# Chipset.net
KiCad netlist of a schematic drawn in Altium Designer
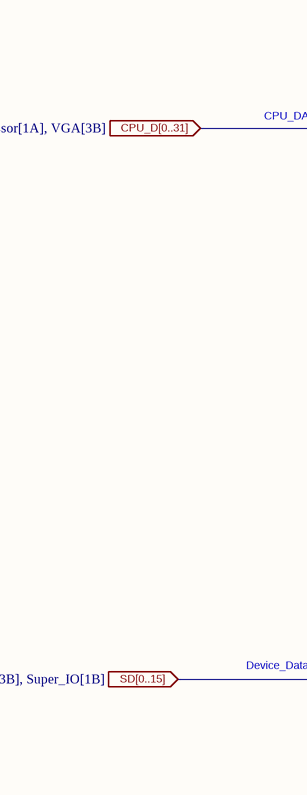
[diagram p0: Chipset.SchDoc, top left]
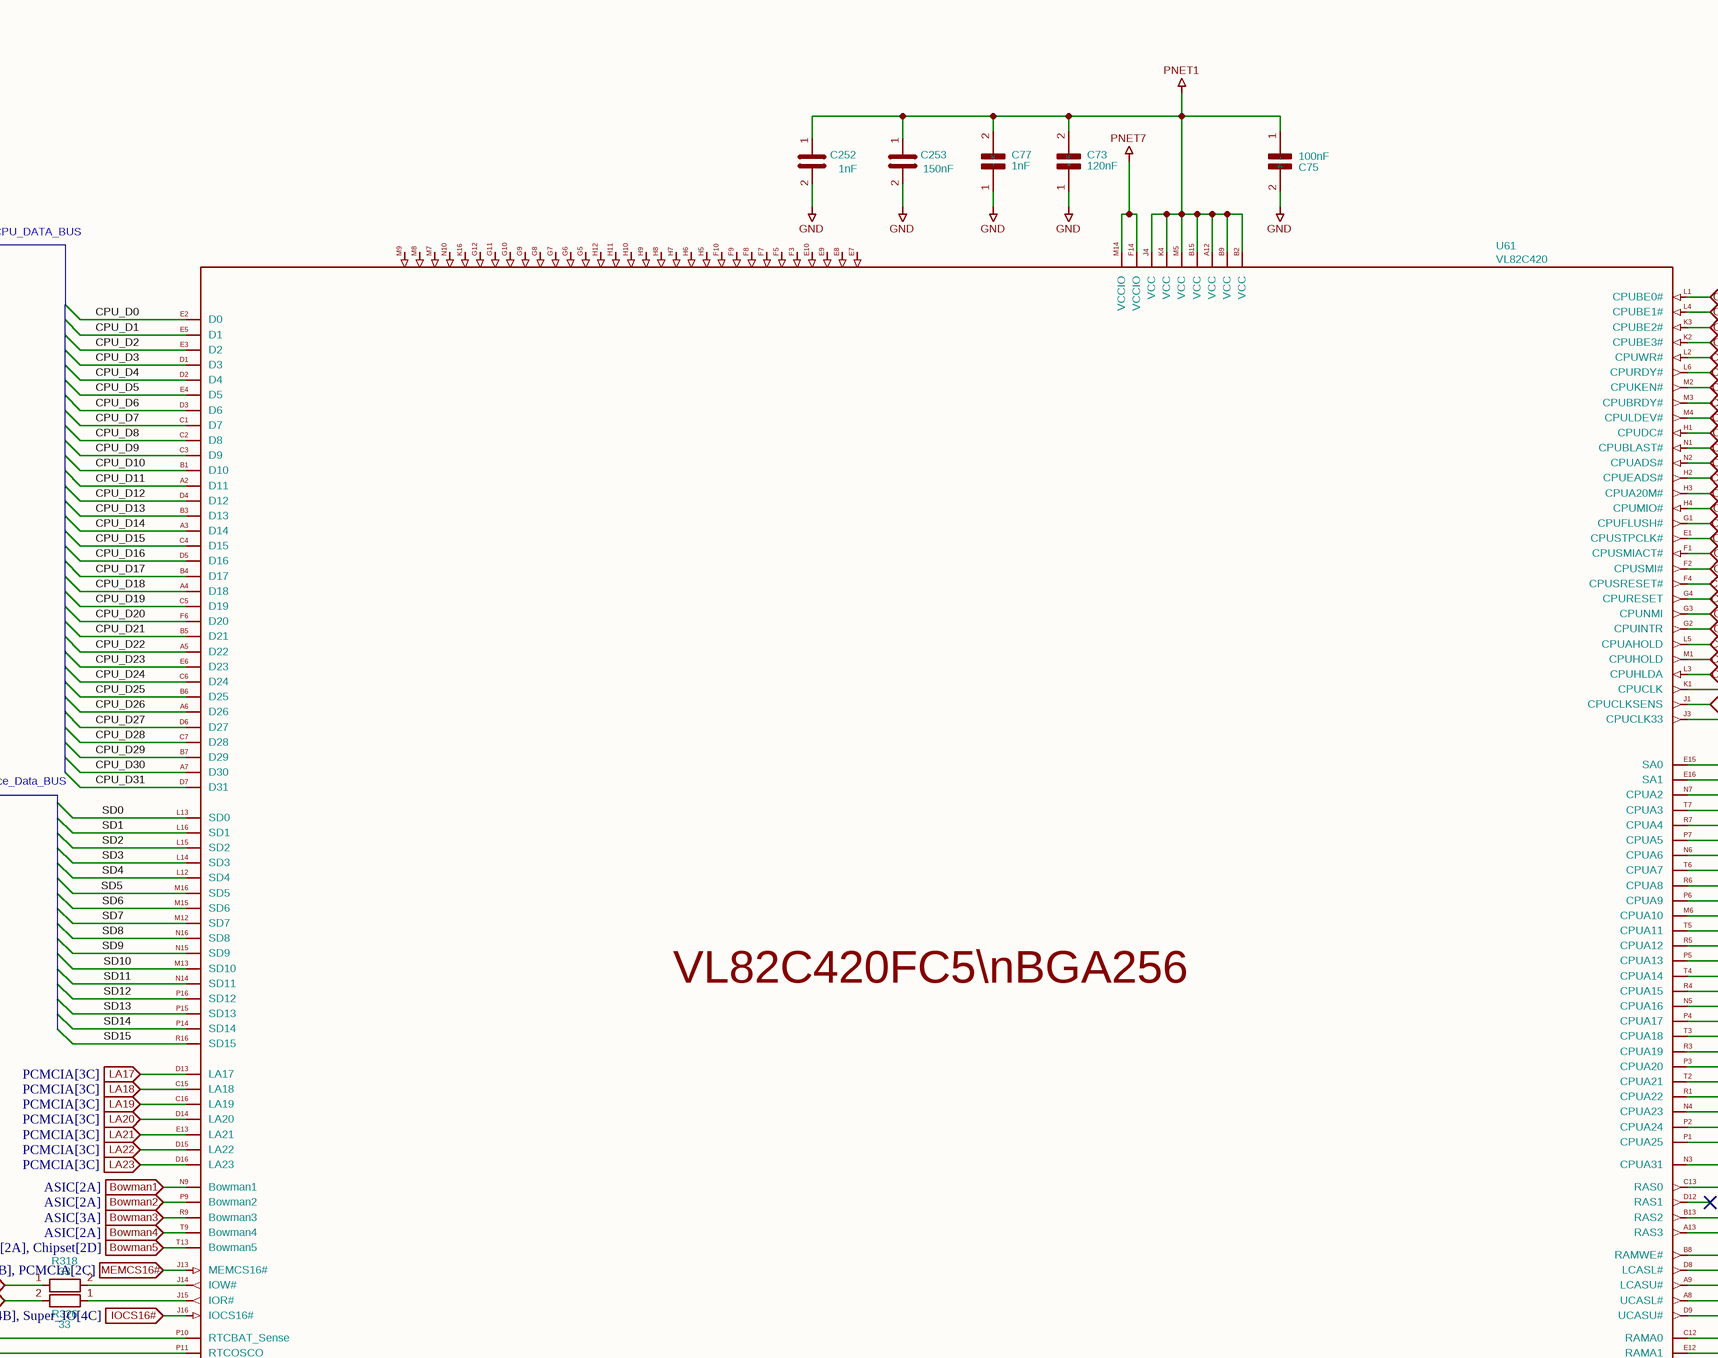
[diagram p1: Chipset.SchDoc, top middle]
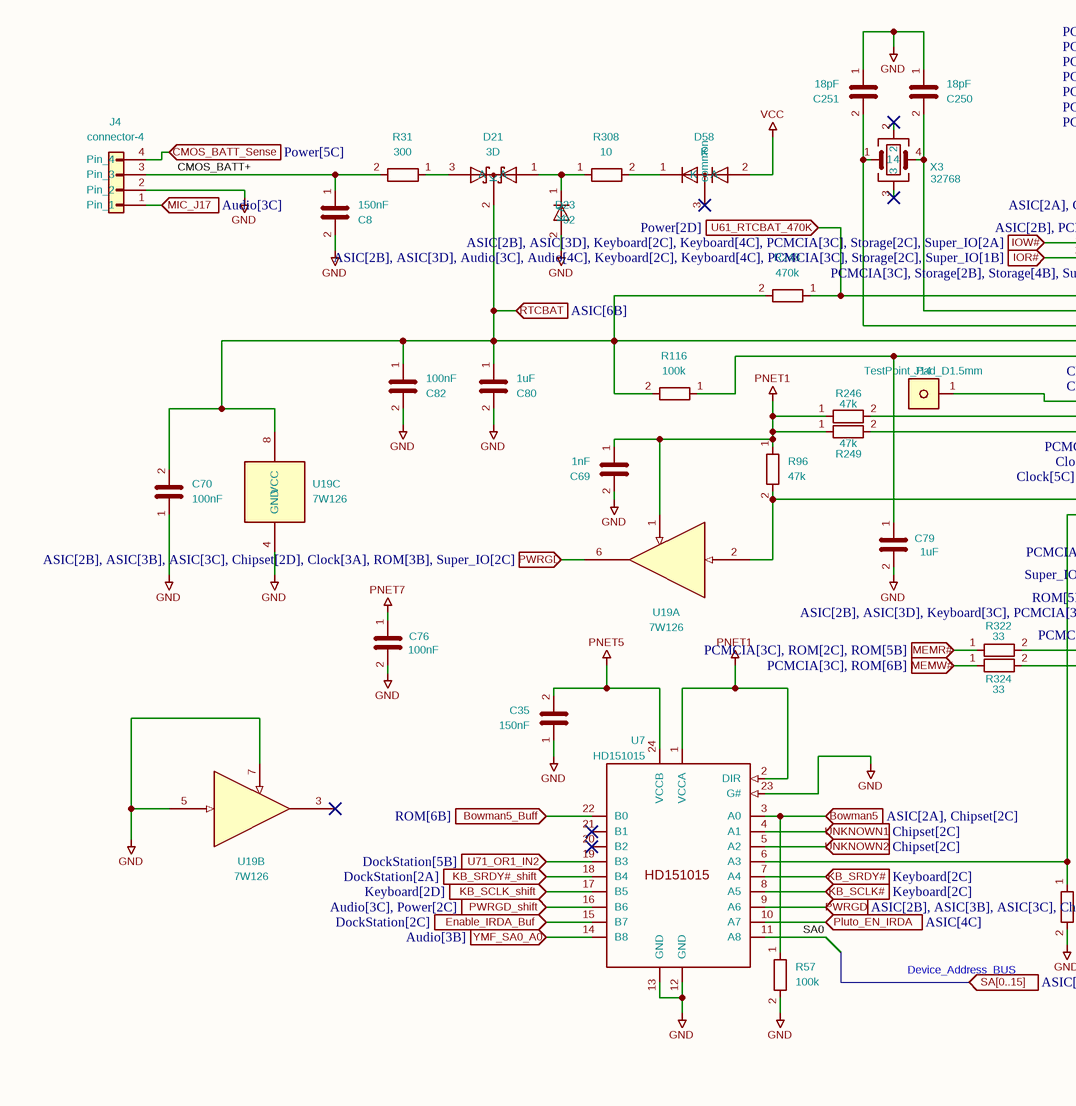
[diagram p2: Chipset.SchDoc, bottom left]
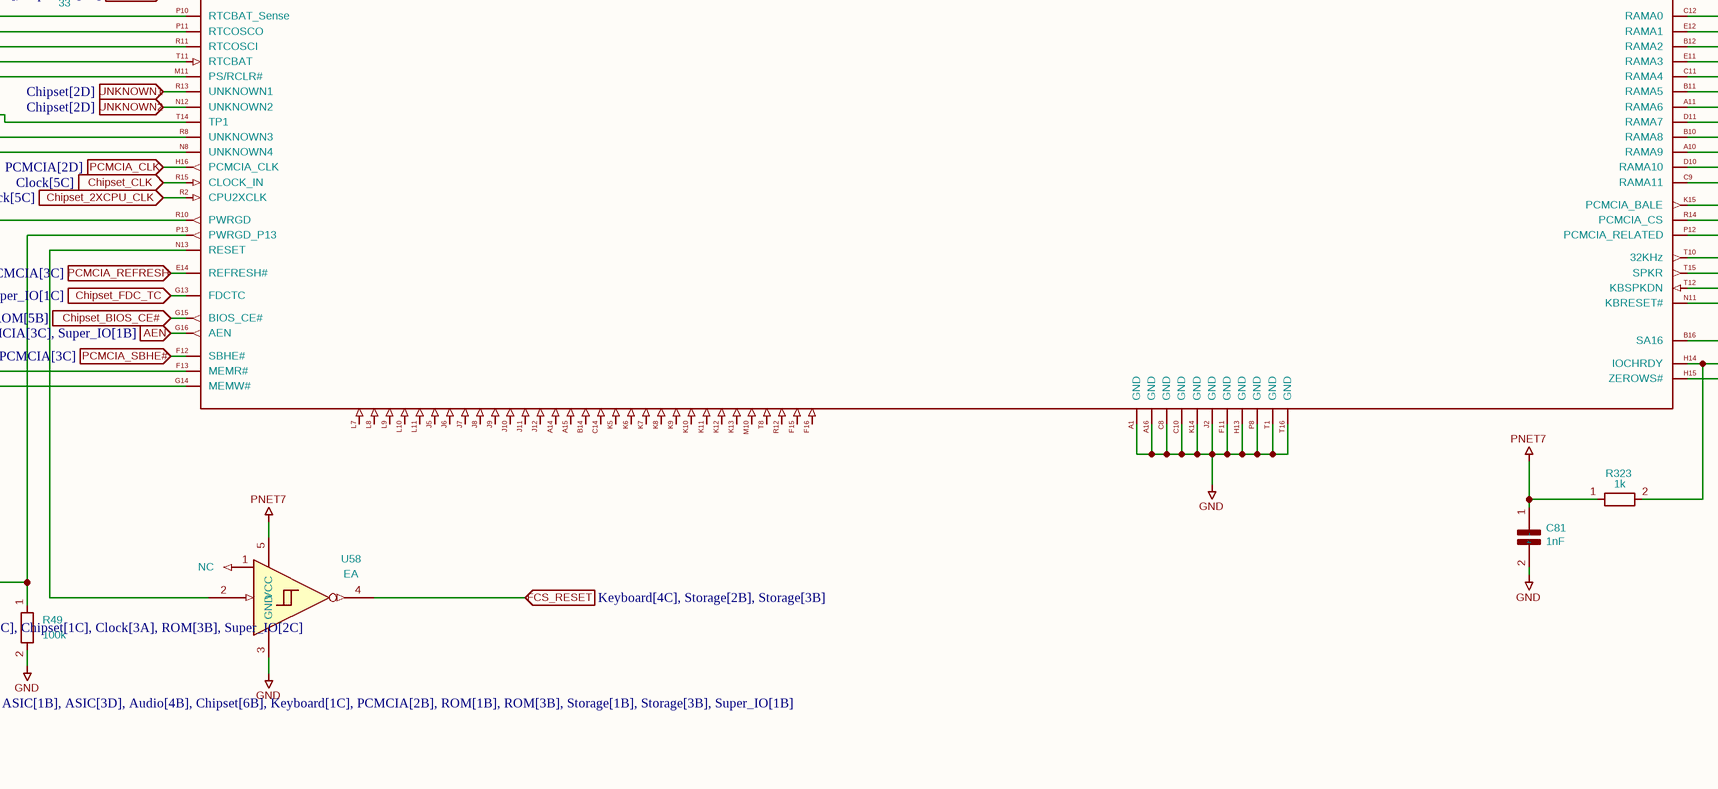
[diagram p3: Chipset.SchDoc, bottom middle]
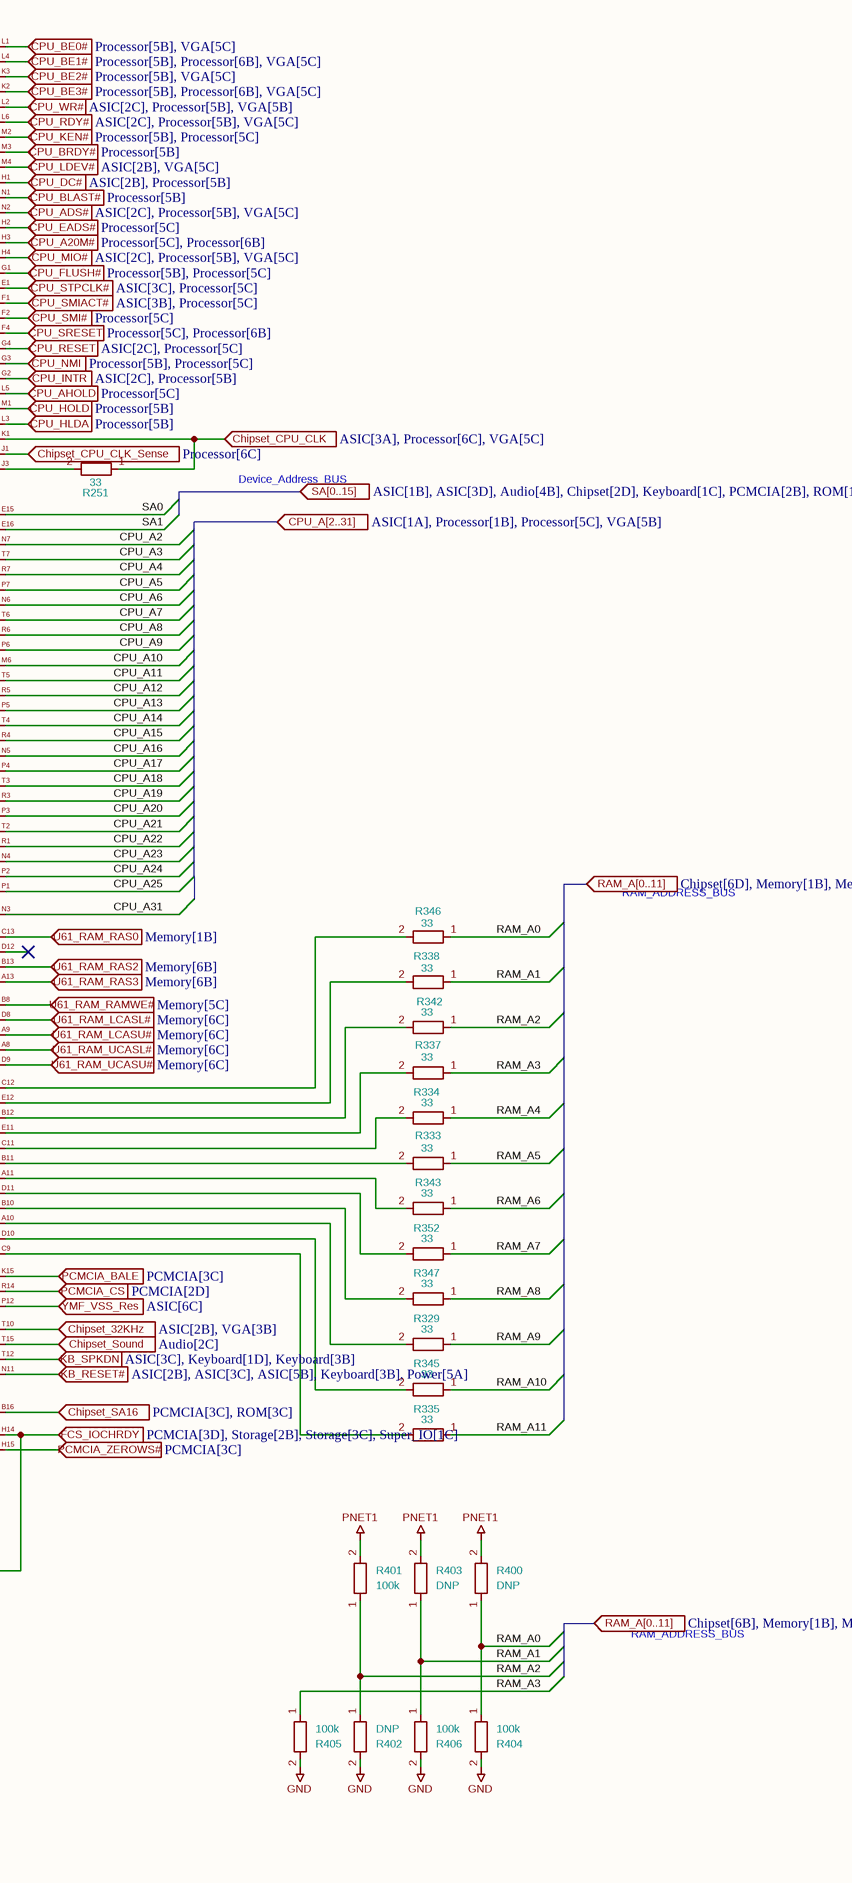
[diagram p4: Chipset.SchDoc, bottom right]

(export (version "E")
  (design (tool "Eeschema 10.0.6"))
  (components
    (comp (ref "C8") (value "150nF") (footprint "C_0402_1005Metric") (libsource (lib "Device") (part "C")))
    (comp (ref "C35") (value "150nF") (footprint "C_0402_1005Metric") (libsource (lib "Device") (part "C")))
    (comp (ref "C69") (value "1nF") (footprint "C_0402_1005Metric") (libsource (lib "Device") (part "C")))
    (comp (ref "C70") (value "100nF") (footprint "C_0402_1005Metric") (libsource (lib "Device") (part "C")))
    (comp (ref "C73") (value "120nF") (footprint "C_0402_1005Metric") (libsource (lib "") (part "C_1")))
    (comp (ref "C75")
      (value "100nF")
      (footprint "C_0402_1005Metric")
      (libsource (lib "PCM_Elektuur") (part "C"))
    )
    (comp (ref "C76") (value "100nF") (footprint "C_0402_1005Metric") (libsource (lib "Device") (part "C")))
    (comp (ref "C77") (value "1nF") (footprint "C_0402_1005Metric") (libsource (lib "") (part "C_1")))
    (comp (ref "C79") (value "1uF") (footprint "C_0603_1608Metric") (libsource (lib "Device") (part "C")))
    (comp (ref "C80") (value "1uF") (footprint "C_0603_1608Metric") (libsource (lib "Device") (part "C")))
    (comp (ref "C81")
      (value "1nF")
      (footprint "C_0402_1005Metric")
      (libsource (lib "PCM_Elektuur") (part "C"))
    )
    (comp (ref "C82") (value "100nF") (footprint "C_0402_1005Metric") (libsource (lib "Device") (part "C")))
    (comp (ref "C250") (value "18pF") (footprint "C_0402_1005Metric") (libsource (lib "Device") (part "C")))
    (comp (ref "C251") (value "18pF") (footprint "C_0402_1005Metric") (libsource (lib "Device") (part "C")))
    (comp (ref "C252") (value "1nF") (footprint "C_0402_1005Metric") (libsource (lib "Device") (part "C")))
    (comp (ref "C253") (value "150nF") (footprint "C_0402_1005Metric") (libsource (lib "Device") (part "C")))
    (comp (ref "D21")
      (value "3D")
      (footprint "3D")
      (libsource (lib "Device") (part "D_Schottky_Dual_CommonCathode_AKA"))
    )
    (comp (ref "D23") (value "92") (footprint "D_0603_1608Metric") (libsource (lib "Device") (part "D")))
    (comp (ref "D58")
      (value "K")
      (footprint "SOT-416L")
      (libsource (lib "Device") (part "D_Dual_Series_KAC"))
    )
    (comp (ref "J4")
      (value "connector-4")
      (footprint "connector-4")
      (libsource (lib "Connector_Generic") (part "Conn_01x04"))
    )
    (comp (ref "J14")
      (value "TestPoint_Pad_D1.5mm")
      (footprint "TestPoint_Pad_D1.5mm")
      (libsource (lib "PC110") (part "Debug1"))
    )
    (comp (ref "R31") (value "300") (footprint "R_0402_1005Metric") (libsource (lib "Device") (part "R")))
    (comp (ref "R49") (value "100k") (footprint "R_0402_1005Metric") (libsource (lib "Device") (part "R")))
    (comp (ref "R57") (value "100k") (footprint "R_0402_1005Metric") (libsource (lib "Device") (part "R")))
    (comp (ref "R96") (value "47k") (footprint "R_0402_1005Metric") (libsource (lib "Device") (part "R")))
    (comp (ref "R116") (value "100k") (footprint "R_0402_1005Metric") (libsource (lib "") (part "R_2")))
    (comp (ref "R246") (value "47k") (footprint "R_0402_1005Metric") (libsource (lib "") (part "R_1")))
    (comp (ref "R248") (value "470k") (footprint "R_0402_1005Metric") (libsource (lib "Device") (part "R")))
    (comp (ref "R249") (value "47k") (footprint "R_0402_1005Metric") (libsource (lib "") (part "R_3")))
    (comp (ref "R251") (value "33") (footprint "R_0402_1005Metric") (libsource (lib "Device") (part "R")))
    (comp (ref "R308") (value "10") (footprint "R_0402_1005Metric") (libsource (lib "") (part "R_3")))
    (comp (ref "R318") (value "33") (footprint "R_0402_1005Metric") (libsource (lib "") (part "R_3")))
    (comp (ref "R322") (value "33") (footprint "R_0402_1005Metric") (libsource (lib "") (part "R_3")))
    (comp (ref "R323") (value "1k") (footprint "R_0402_1005Metric") (libsource (lib "") (part "R_3")))
    (comp (ref "R324") (value "33") (footprint "R_0402_1005Metric") (libsource (lib "") (part "R_1")))
    (comp (ref "R326") (value "33") (footprint "R_0402_1005Metric") (libsource (lib "") (part "R_2")))
    (comp (ref "R329") (value "33") (footprint "R_0402_1005Metric") (libsource (lib "Device") (part "R")))
    (comp (ref "R333") (value "33") (footprint "R_0402_1005Metric") (libsource (lib "Device") (part "R")))
    (comp (ref "R334") (value "33") (footprint "R_0402_1005Metric") (libsource (lib "Device") (part "R")))
    (comp (ref "R335") (value "33") (footprint "R_0402_1005Metric") (libsource (lib "Device") (part "R")))
    (comp (ref "R337") (value "33") (footprint "R_0402_1005Metric") (libsource (lib "Device") (part "R")))
    (comp (ref "R338") (value "33") (footprint "R_0402_1005Metric") (libsource (lib "Device") (part "R")))
    (comp (ref "R342") (value "33") (footprint "R_0402_1005Metric") (libsource (lib "Device") (part "R")))
    (comp (ref "R343") (value "33") (footprint "R_0402_1005Metric") (libsource (lib "Device") (part "R")))
    (comp (ref "R345") (value "33") (footprint "R_0402_1005Metric") (libsource (lib "Device") (part "R")))
    (comp (ref "R346") (value "33") (footprint "R_0402_1005Metric") (libsource (lib "Device") (part "R")))
    (comp (ref "R347") (value "33") (footprint "R_0402_1005Metric") (libsource (lib "Device") (part "R")))
    (comp (ref "R352") (value "33") (footprint "R_0402_1005Metric") (libsource (lib "Device") (part "R")))
    (comp (ref "R400") (value "DNP") (footprint "R_0402_1005Metric") (libsource (lib "") (part "R_1")))
    (comp (ref "R401") (value "100k") (footprint "R_0402_1005Metric") (libsource (lib "") (part "R_1")))
    (comp (ref "R402") (value "DNP") (footprint "R_0402_1005Metric") (libsource (lib "") (part "R_2")))
    (comp (ref "R403") (value "DNP") (footprint "R_0402_1005Metric") (libsource (lib "") (part "R_1")))
    (comp (ref "R404") (value "100k") (footprint "R_0402_1005Metric") (libsource (lib "") (part "R_2")))
    (comp (ref "R405") (value "100k") (footprint "R_0402_1005Metric") (libsource (lib "") (part "R_2")))
    (comp (ref "R406") (value "100k") (footprint "R_0402_1005Metric") (libsource (lib "") (part "R_2")))
    (comp (ref "U7")
      (value "HD151015")
      (footprint "TSSOP-24_6.1x7.8mm_P0.65mm")
      (libsource (lib "PC110") (part "HD151015"))
    )
    (comp (ref "U19") (value "7W126") (footprint "sso-8") (libsource (lib "74xGxx") (part "74AUC2G126")))
    (comp (ref "U58") (value "EA") (footprint "SOT-353") (libsource (lib "74xGxx") (part "74AHC1G14")))
    (comp (ref "U61") (value "VL82C420") (footprint "BGA-256") (libsource (lib "PC110") (part "VL82C420")))
    (comp (ref "X3") (value "32768") (footprint "XTAL-3") (libsource (lib "Device") (part "Crystal_GND23")))
  )
  (nets
    (net (code "20") (name "/AEN") (class "Default")
      (node (ref "U61") (pin "G16") (pinfunction "AEN_G16") (pintype "output"))
    )
    (net (code "21") (name "/Bowman1") (class "Default")
      (node (ref "U61") (pin "N9") (pinfunction "Bowman1_N9") (pintype "bidirectional"))
    )
    (net (code "22") (name "/Bowman2") (class "Default")
      (node (ref "U61") (pin "P9") (pinfunction "Bowman2_P9") (pintype "bidirectional"))
    )
    (net (code "23") (name "/Bowman3") (class "Default")
      (node (ref "U61") (pin "R9") (pinfunction "Bowman3_R9") (pintype "bidirectional"))
    )
    (net (code "24") (name "/Bowman4") (class "Default")
      (node (ref "U61") (pin "T9") (pinfunction "Bowman4_T9") (pintype "bidirectional"))
    )
    (net (code "25") (name "/Bowman5") (class "Default")
      (node (ref "R57") (pin "1") (pinfunction "1_1") (pintype "passive"))
      (node (ref "U61") (pin "T13") (pinfunction "Bowman5_T13") (pintype "bidirectional"))
      (node (ref "U7") (pin "3") (pinfunction "A0_3") (pintype "bidirectional"))
    )
    (net (code "26") (name "/Bowman5_Buff") (class "Default")
      (node (ref "U7") (pin "22") (pinfunction "B0_22") (pintype "bidirectional"))
    )
    (net (code "27") (name "/CMOS_BATT+") (class "Default")
      (node (ref "C8") (pin "1") (pinfunction "1_1") (pintype "passive"))
      (node (ref "J4") (pin "3") (pinfunction "Pin_3_3") (pintype "passive"))
      (node (ref "R31") (pin "2") (pinfunction "2_2") (pintype "passive"))
    )
    (net (code "28") (name "/CMOS_BATT_Sense") (class "Default")
      (node (ref "J4") (pin "4") (pinfunction "Pin_4_4") (pintype "passive"))
    )
    (net (code "29") (name "/CPU_A2") (class "Default")
      (node (ref "U61") (pin "N7") (pinfunction "CPUA2_N7") (pintype "bidirectional"))
    )
    (net (code "30") (name "/CPU_A3") (class "Default")
      (node (ref "U61") (pin "T7") (pinfunction "CPUA3_T7") (pintype "bidirectional"))
    )
    (net (code "31") (name "/CPU_A4") (class "Default")
      (node (ref "U61") (pin "R7") (pinfunction "CPUA4_R7") (pintype "bidirectional"))
    )
    (net (code "32") (name "/CPU_A5") (class "Default")
      (node (ref "U61") (pin "P7") (pinfunction "CPUA5_P7") (pintype "bidirectional"))
    )
    (net (code "33") (name "/CPU_A6") (class "Default")
      (node (ref "U61") (pin "N6") (pinfunction "CPUA6_N6") (pintype "bidirectional"))
    )
    (net (code "34") (name "/CPU_A7") (class "Default")
      (node (ref "U61") (pin "T6") (pinfunction "CPUA7_T6") (pintype "bidirectional"))
    )
    (net (code "35") (name "/CPU_A8") (class "Default")
      (node (ref "U61") (pin "R6") (pinfunction "CPUA8_R6") (pintype "bidirectional"))
    )
    (net (code "36") (name "/CPU_A9") (class "Default")
      (node (ref "U61") (pin "P6") (pinfunction "CPUA9_P6") (pintype "bidirectional"))
    )
    (net (code "37") (name "/CPU_A10") (class "Default")
      (node (ref "U61") (pin "M6") (pinfunction "CPUA10_M6") (pintype "bidirectional"))
    )
    (net (code "38") (name "/CPU_A11") (class "Default")
      (node (ref "U61") (pin "T5") (pinfunction "CPUA11_T5") (pintype "bidirectional"))
    )
    (net (code "39") (name "/CPU_A12") (class "Default")
      (node (ref "U61") (pin "R5") (pinfunction "CPUA12_R5") (pintype "bidirectional"))
    )
    (net (code "40") (name "/CPU_A13") (class "Default")
      (node (ref "U61") (pin "P5") (pinfunction "CPUA13_P5") (pintype "bidirectional"))
    )
    (net (code "41") (name "/CPU_A14") (class "Default")
      (node (ref "U61") (pin "T4") (pinfunction "CPUA14_T4") (pintype "bidirectional"))
    )
    (net (code "42") (name "/CPU_A15") (class "Default")
      (node (ref "U61") (pin "R4") (pinfunction "CPUA15_R4") (pintype "bidirectional"))
    )
    (net (code "43") (name "/CPU_A16") (class "Default")
      (node (ref "U61") (pin "N5") (pinfunction "CPUA16_N5") (pintype "bidirectional"))
    )
    (net (code "44") (name "/CPU_A17") (class "Default")
      (node (ref "U61") (pin "P4") (pinfunction "CPUA17_P4") (pintype "bidirectional"))
    )
    (net (code "45") (name "/CPU_A18") (class "Default")
      (node (ref "U61") (pin "T3") (pinfunction "CPUA18_T3") (pintype "bidirectional"))
    )
    (net (code "46") (name "/CPU_A19") (class "Default")
      (node (ref "U61") (pin "R3") (pinfunction "CPUA19_R3") (pintype "bidirectional"))
    )
    (net (code "47") (name "/CPU_A20") (class "Default")
      (node (ref "U61") (pin "P3") (pinfunction "CPUA20_P3") (pintype "bidirectional"))
    )
    (net (code "48") (name "/CPU_A20M#") (class "Default")
      (node (ref "U61") (pin "H3") (pinfunction "CPUA20M#_H3") (pintype "output"))
    )
    (net (code "49") (name "/CPU_A21") (class "Default")
      (node (ref "U61") (pin "T2") (pinfunction "CPUA21_T2") (pintype "bidirectional"))
    )
    (net (code "50") (name "/CPU_A22") (class "Default")
      (node (ref "U61") (pin "R1") (pinfunction "CPUA22_R1") (pintype "bidirectional"))
    )
    (net (code "51") (name "/CPU_A23") (class "Default")
      (node (ref "U61") (pin "N4") (pinfunction "CPUA23_N4") (pintype "bidirectional"))
    )
    (net (code "52") (name "/CPU_A24") (class "Default")
      (node (ref "U61") (pin "P2") (pinfunction "CPUA24_P2") (pintype "bidirectional"))
    )
    (net (code "53") (name "/CPU_A25") (class "Default")
      (node (ref "U61") (pin "P1") (pinfunction "CPUA25_P1") (pintype "bidirectional"))
    )
    (net (code "54") (name "/CPU_A31") (class "Default")
      (node (ref "U61") (pin "N3") (pinfunction "CPUA31_N3") (pintype "bidirectional"))
    )
    (net (code "55") (name "/CPU_ADS#") (class "Default")
      (node (ref "U61") (pin "N2") (pinfunction "CPUADS#_N2") (pintype "input"))
    )
    (net (code "56") (name "/CPU_AHOLD") (class "Default")
      (node (ref "U61") (pin "L5") (pinfunction "CPUAHOLD_L5") (pintype "output"))
    )
    (net (code "58") (name "/CPU_BE0#") (class "Default")
      (node (ref "U61") (pin "L1") (pinfunction "CPUBE0#_L1") (pintype "input"))
    )
    (net (code "59") (name "/CPU_BE1#") (class "Default")
      (node (ref "U61") (pin "L4") (pinfunction "CPUBE1#_L4") (pintype "input"))
    )
    (net (code "60") (name "/CPU_BE2#") (class "Default")
      (node (ref "U61") (pin "K3") (pinfunction "CPUBE2#_K3") (pintype "input"))
    )
    (net (code "61") (name "/CPU_BE3#") (class "Default")
      (node (ref "U61") (pin "K2") (pinfunction "CPUBE3#_K2") (pintype "input"))
    )
    (net (code "62") (name "/CPU_BLAST#") (class "Default")
      (node (ref "U61") (pin "N1") (pinfunction "CPUBLAST#_N1") (pintype "input"))
    )
    (net (code "63") (name "/CPU_BRDY#") (class "Default")
      (node (ref "U61") (pin "M3") (pinfunction "CPUBRDY#_M3") (pintype "output"))
    )
    (net (code "64") (name "/CPU_D0") (class "Default")
      (node (ref "U61") (pin "E2") (pinfunction "D0_E2") (pintype "bidirectional"))
    )
    (net (code "65") (name "/CPU_D1") (class "Default")
      (node (ref "U61") (pin "E5") (pinfunction "D1_E5") (pintype "bidirectional"))
    )
    (net (code "66") (name "/CPU_D2") (class "Default")
      (node (ref "U61") (pin "E3") (pinfunction "D2_E3") (pintype "bidirectional"))
    )
    (net (code "67") (name "/CPU_D3") (class "Default")
      (node (ref "U61") (pin "D1") (pinfunction "D3_D1") (pintype "bidirectional"))
    )
    (net (code "68") (name "/CPU_D4") (class "Default")
      (node (ref "U61") (pin "D2") (pinfunction "D4_D2") (pintype "bidirectional"))
    )
    (net (code "69") (name "/CPU_D5") (class "Default")
      (node (ref "U61") (pin "E4") (pinfunction "D5_E4") (pintype "bidirectional"))
    )
    (net (code "70") (name "/CPU_D6") (class "Default")
      (node (ref "U61") (pin "D3") (pinfunction "D6_D3") (pintype "bidirectional"))
    )
    (net (code "71") (name "/CPU_D7") (class "Default")
      (node (ref "U61") (pin "C1") (pinfunction "D7_C1") (pintype "bidirectional"))
    )
    (net (code "72") (name "/CPU_D8") (class "Default")
      (node (ref "U61") (pin "C2") (pinfunction "D8_C2") (pintype "bidirectional"))
    )
    (net (code "73") (name "/CPU_D9") (class "Default")
      (node (ref "U61") (pin "C3") (pinfunction "D9_C3") (pintype "bidirectional"))
    )
    (net (code "74") (name "/CPU_D10") (class "Default")
      (node (ref "U61") (pin "B1") (pinfunction "D10_B1") (pintype "bidirectional"))
    )
    (net (code "75") (name "/CPU_D11") (class "Default")
      (node (ref "U61") (pin "A2") (pinfunction "D11_A2") (pintype "bidirectional"))
    )
    (net (code "76") (name "/CPU_D12") (class "Default")
      (node (ref "U61") (pin "D4") (pinfunction "D12_D4") (pintype "bidirectional"))
    )
    (net (code "77") (name "/CPU_D13") (class "Default")
      (node (ref "U61") (pin "B3") (pinfunction "D13_B3") (pintype "bidirectional"))
    )
    (net (code "78") (name "/CPU_D14") (class "Default")
      (node (ref "U61") (pin "A3") (pinfunction "D14_A3") (pintype "bidirectional"))
    )
    (net (code "79") (name "/CPU_D15") (class "Default")
      (node (ref "U61") (pin "C4") (pinfunction "D15_C4") (pintype "bidirectional"))
    )
    (net (code "80") (name "/CPU_D16") (class "Default")
      (node (ref "U61") (pin "D5") (pinfunction "D16_D5") (pintype "bidirectional"))
    )
    (net (code "81") (name "/CPU_D17") (class "Default")
      (node (ref "U61") (pin "B4") (pinfunction "D17_B4") (pintype "bidirectional"))
    )
    (net (code "82") (name "/CPU_D18") (class "Default")
      (node (ref "U61") (pin "A4") (pinfunction "D18_A4") (pintype "bidirectional"))
    )
    (net (code "83") (name "/CPU_D19") (class "Default")
      (node (ref "U61") (pin "C5") (pinfunction "D19_C5") (pintype "bidirectional"))
    )
    (net (code "84") (name "/CPU_D20") (class "Default")
      (node (ref "U61") (pin "F6") (pinfunction "D20_F6") (pintype "bidirectional"))
    )
    (net (code "85") (name "/CPU_D21") (class "Default")
      (node (ref "U61") (pin "B5") (pinfunction "D21_B5") (pintype "bidirectional"))
    )
    (net (code "86") (name "/CPU_D22") (class "Default")
      (node (ref "U61") (pin "A5") (pinfunction "D22_A5") (pintype "bidirectional"))
    )
    (net (code "87") (name "/CPU_D23") (class "Default")
      (node (ref "U61") (pin "E6") (pinfunction "D23_E6") (pintype "bidirectional"))
    )
    (net (code "88") (name "/CPU_D24") (class "Default")
      (node (ref "U61") (pin "C6") (pinfunction "D24_C6") (pintype "bidirectional"))
    )
    (net (code "89") (name "/CPU_D25") (class "Default")
      (node (ref "U61") (pin "B6") (pinfunction "D25_B6") (pintype "bidirectional"))
    )
    (net (code "90") (name "/CPU_D26") (class "Default")
      (node (ref "U61") (pin "A6") (pinfunction "D26_A6") (pintype "bidirectional"))
    )
    (net (code "91") (name "/CPU_D27") (class "Default")
      (node (ref "U61") (pin "D6") (pinfunction "D27_D6") (pintype "bidirectional"))
    )
    (net (code "92") (name "/CPU_D28") (class "Default")
      (node (ref "U61") (pin "C7") (pinfunction "D28_C7") (pintype "bidirectional"))
    )
    (net (code "93") (name "/CPU_D29") (class "Default")
      (node (ref "U61") (pin "B7") (pinfunction "D29_B7") (pintype "bidirectional"))
    )
    (net (code "94") (name "/CPU_D30") (class "Default")
      (node (ref "U61") (pin "A7") (pinfunction "D30_A7") (pintype "bidirectional"))
    )
    (net (code "95") (name "/CPU_D31") (class "Default")
      (node (ref "U61") (pin "D7") (pinfunction "D31_D7") (pintype "bidirectional"))
    )
    (net (code "96") (name "/CPU_DC#") (class "Default")
      (node (ref "U61") (pin "H1") (pinfunction "CPUDC#_H1") (pintype "input"))
    )
    (net (code "98") (name "/CPU_EADS#") (class "Default")
      (node (ref "U61") (pin "H2") (pinfunction "CPUEADS#_H2") (pintype "output"))
    )
    (net (code "99") (name "/CPU_FLUSH#") (class "Default")
      (node (ref "U61") (pin "G1") (pinfunction "CPUFLUSH#_G1") (pintype "output"))
    )
    (net (code "100") (name "/CPU_HLDA") (class "Default")
      (node (ref "U61") (pin "L3") (pinfunction "CPUHLDA_L3") (pintype "input"))
    )
    (net (code "101") (name "/CPU_HOLD") (class "Default")
      (node (ref "U61") (pin "M1") (pinfunction "CPUHOLD_M1") (pintype "output"))
    )
    (net (code "102") (name "/CPU_INTR") (class "Default")
      (node (ref "U61") (pin "G2") (pinfunction "CPUINTR_G2") (pintype "output"))
    )
    (net (code "103") (name "/CPU_KEN#") (class "Default")
      (node (ref "U61") (pin "M2") (pinfunction "CPUKEN#_M2") (pintype "output"))
    )
    (net (code "104") (name "/CPU_LDEV#") (class "Default")
      (node (ref "U61") (pin "M4") (pinfunction "CPULDEV#_M4") (pintype "output"))
    )
    (net (code "105") (name "/CPU_MIO#") (class "Default")
      (node (ref "U61") (pin "H4") (pinfunction "CPUMIO#_H4") (pintype "input"))
    )
    (net (code "106") (name "/CPU_NMI") (class "Default")
      (node (ref "U61") (pin "G3") (pinfunction "CPUNMI_G3") (pintype "output"))
    )
    (net (code "107") (name "/CPU_RDY#") (class "Default")
      (node (ref "U61") (pin "L6") (pinfunction "CPURDY#_L6") (pintype "output"))
    )
    (net (code "108") (name "/CPU_RESET") (class "Default")
      (node (ref "U61") (pin "G4") (pinfunction "CPURESET_G4") (pintype "output"))
    )
    (net (code "109") (name "/CPU_SMI#") (class "Default")
      (node (ref "U61") (pin "F2") (pinfunction "CPUSMI#_F2") (pintype "output"))
    )
    (net (code "110") (name "/CPU_SMIACT#") (class "Default")
      (node (ref "U61") (pin "F1") (pinfunction "CPUSMIACT#_F1") (pintype "input"))
    )
    (net (code "111") (name "/CPU_SRESET") (class "Default")
      (node (ref "U61") (pin "F4") (pinfunction "CPUSRESET#_F4") (pintype "output"))
    )
    (net (code "112") (name "/CPU_STPCLK#") (class "Default")
      (node (ref "U61") (pin "E1") (pinfunction "CPUSTPCLK#_E1") (pintype "output"))
    )
    (net (code "113") (name "/CPU_WR#") (class "Default")
      (node (ref "U61") (pin "L2") (pinfunction "CPUWR#_L2") (pintype "input"))
    )
    (net (code "114") (name "/Chipset_2XCPU_CLK") (class "Default")
      (node (ref "U61") (pin "R2") (pinfunction "CPU2XCLK_R2") (pintype "input"))
    )
    (net (code "115") (name "/Chipset_32KHz") (class "Default")
      (node (ref "U61") (pin "T10") (pinfunction "32KHz_T10") (pintype "output"))
    )
    (net (code "116") (name "/Chipset_BIOS_CE#") (class "Default")
      (node (ref "U61") (pin "G15") (pinfunction "BIOS_CE#_G15") (pintype "output"))
    )
    (net (code "117") (name "/Chipset_CLK") (class "Default")
      (node (ref "U61") (pin "R15") (pinfunction "CLOCK_IN_R15") (pintype "input"))
    )
    (net (code "118") (name "/Chipset_CPU_CLK") (class "Default")
      (node (ref "R251") (pin "1") (pinfunction "1_1") (pintype "passive"))
      (node (ref "U61") (pin "K1") (pinfunction "CPUCLK_K1") (pintype "output"))
    )
    (net (code "119") (name "/Chipset_CPU_CLK_Sense") (class "Default")
      (node (ref "U61") (pin "J1") (pinfunction "CPUCLKSENS_J1") (pintype "output"))
    )
    (net (code "120") (name "/Chipset_FDC_TC") (class "Default")
      (node (ref "U61") (pin "G13") (pinfunction "FDCTC_G13") (pintype "bidirectional"))
    )
    (net (code "121") (name "/Chipset_SA16") (class "Default")
      (node (ref "U61") (pin "B16") (pinfunction "SA16_B16") (pintype "bidirectional"))
    )
    (net (code "122") (name "/Chipset_Sound") (class "Default")
      (node (ref "U61") (pin "T15") (pinfunction "SPKR_T15") (pintype "output"))
    )
    (net (code "123") (name "/Enable_IRDA_Buf") (class "Default")
      (node (ref "U7") (pin "15") (pinfunction "B7_15") (pintype "bidirectional"))
    )
    (net (code "124") (name "/FCS_IOCHRDY") (class "Default")
      (node (ref "R323") (pin "2") (pinfunction "2_2") (pintype "passive"))
      (node (ref "U61") (pin "H14") (pinfunction "IOCHRDY_H14") (pintype "bidirectional"))
    )
    (net (code "125") (name "/FCS_RESET") (class "Default")
      (node (ref "U58") (pin "4") (pinfunction "4_4") (pintype "output"))
    )
    (net (code "126") (name "/IOCS16#") (class "Default")
      (node (ref "U61") (pin "J16") (pinfunction "IOCS16#_J16") (pintype "input"))
    )
    (net (code "127") (name "/IOR#") (class "Default")
      (node (ref "R326") (pin "2") (pinfunction "2_2") (pintype "passive"))
    )
    (net (code "128") (name "/IOW#") (class "Default")
      (node (ref "R318") (pin "1") (pinfunction "1_1") (pintype "passive"))
    )
    (net (code "129") (name "/KB_RESET#") (class "Default")
      (node (ref "U61") (pin "N11") (pinfunction "KBRESET#_N11") (pintype "bidirectional"))
    )
    (net (code "130") (name "/KB_SCLK#") (class "Default")
      (node (ref "U7") (pin "8") (pinfunction "A5_8") (pintype "bidirectional"))
    )
    (net (code "131") (name "/KB_SCLK_shift") (class "Default")
      (node (ref "U7") (pin "17") (pinfunction "B5_17") (pintype "bidirectional"))
    )
    (net (code "132") (name "/KB_SPKDN") (class "Default")
      (node (ref "U61") (pin "T12") (pinfunction "KBSPKDN_T12") (pintype "input"))
    )
    (net (code "133") (name "/KB_SRDY#") (class "Default")
      (node (ref "U7") (pin "7") (pinfunction "A4_7") (pintype "bidirectional"))
    )
    (net (code "134") (name "/KB_SRDY#_shift") (class "Default")
      (node (ref "U7") (pin "18") (pinfunction "B4_18") (pintype "bidirectional"))
    )
    (net (code "135") (name "/LA17") (class "Default")
      (node (ref "U61") (pin "D13") (pinfunction "LA17_D13") (pintype "bidirectional"))
    )
    (net (code "136") (name "/LA18") (class "Default")
      (node (ref "U61") (pin "C15") (pinfunction "LA18_C15") (pintype "bidirectional"))
    )
    (net (code "137") (name "/LA19") (class "Default")
      (node (ref "U61") (pin "C16") (pinfunction "LA19_C16") (pintype "bidirectional"))
    )
    (net (code "138") (name "/LA20") (class "Default")
      (node (ref "U61") (pin "D14") (pinfunction "LA20_D14") (pintype "bidirectional"))
    )
    (net (code "139") (name "/LA21") (class "Default")
      (node (ref "U61") (pin "E13") (pinfunction "LA21_E13") (pintype "bidirectional"))
    )
    (net (code "140") (name "/LA22") (class "Default")
      (node (ref "U61") (pin "D15") (pinfunction "LA22_D15") (pintype "bidirectional"))
    )
    (net (code "141") (name "/LA23") (class "Default")
      (node (ref "U61") (pin "D16") (pinfunction "LA23_D16") (pintype "bidirectional"))
    )
    (net (code "142") (name "/MEMCS16#") (class "Default")
      (node (ref "U61") (pin "J13") (pinfunction "MEMCS16#_J13") (pintype "input"))
    )
    (net (code "143") (name "/MEMR#") (class "Default")
      (node (ref "R322") (pin "1") (pinfunction "1_1") (pintype "passive"))
    )
    (net (code "144") (name "/MEMW#") (class "Default")
      (node (ref "R324") (pin "1") (pinfunction "1_1") (pintype "passive"))
    )
    (net (code "145") (name "/MIC_J17") (class "Default")
      (node (ref "J4") (pin "1") (pinfunction "Pin_1_1") (pintype "passive"))
    )
    (net (code "146") (name "/PCMCIA_BALE") (class "Default")
      (node (ref "U61") (pin "K15") (pinfunction "PCMCIA_BALE_K15") (pintype "output"))
    )
    (net (code "147") (name "/PCMCIA_CLK") (class "Default")
      (node (ref "U61") (pin "H16") (pinfunction "PCMCIA_CLK_H16") (pintype "output"))
    )
    (net (code "148") (name "/PCMCIA_CS") (class "Default")
      (node (ref "U61") (pin "R14") (pinfunction "PCMCIA_CS_R14") (pintype "bidirectional"))
    )
    (net (code "149") (name "/PCMCIA_REFRESH") (class "Default")
      (node (ref "U61") (pin "E14") (pinfunction "REFRESH#_E14") (pintype "bidirectional"))
    )
    (net (code "150") (name "/PCMCIA_SBHE#") (class "Default")
      (node (ref "U61") (pin "F12") (pinfunction "SBHE#_F12") (pintype "bidirectional"))
    )
    (net (code "151") (name "/PCMCIA_ZEROWS#") (class "Default")
      (node (ref "U61") (pin "H15") (pinfunction "ZEROWS#_H15") (pintype "bidirectional"))
    )
    (net (code "152") (name "/PWRGD") (class "Default")
      (node (ref "U19") (pin "6") (pinfunction "6_6") (pintype "tri_state"))
      (node (ref "U7") (pin "9") (pinfunction "A6_9") (pintype "bidirectional"))
    )
    (net (code "153") (name "/PWRGD_shift") (class "Default")
      (node (ref "U7") (pin "16") (pinfunction "B6_16") (pintype "bidirectional"))
    )
    (net (code "154") (name "/Pluto_EN_IRDA") (class "Default")
      (node (ref "U7") (pin "10") (pinfunction "A7_10") (pintype "bidirectional"))
    )
    (net (code "155") (name "/RAM_A0") (class "Default")
      (node (ref "R346") (pin "1") (pinfunction "1_1") (pintype "passive"))
      (node (ref "R400") (pin "1") (pinfunction "1_1") (pintype "passive"))
      (node (ref "R404") (pin "1") (pinfunction "1_1") (pintype "passive"))
    )
    (net (code "156") (name "/RAM_A1") (class "Default")
      (node (ref "R338") (pin "1") (pinfunction "1_1") (pintype "passive"))
      (node (ref "R403") (pin "1") (pinfunction "1_1") (pintype "passive"))
      (node (ref "R406") (pin "1") (pinfunction "1_1") (pintype "passive"))
    )
    (net (code "157") (name "/RAM_A2") (class "Default")
      (node (ref "R342") (pin "1") (pinfunction "1_1") (pintype "passive"))
      (node (ref "R401") (pin "1") (pinfunction "1_1") (pintype "passive"))
      (node (ref "R402") (pin "1") (pinfunction "1_1") (pintype "passive"))
    )
    (net (code "158") (name "/RAM_A3") (class "Default")
      (node (ref "R337") (pin "1") (pinfunction "1_1") (pintype "passive"))
      (node (ref "R405") (pin "1") (pinfunction "1_1") (pintype "passive"))
    )
    (net (code "159") (name "/RAM_A4") (class "Default")
      (node (ref "R334") (pin "1") (pinfunction "1_1") (pintype "passive"))
    )
    (net (code "160") (name "/RAM_A5") (class "Default")
      (node (ref "R333") (pin "1") (pinfunction "1_1") (pintype "passive"))
    )
    (net (code "161") (name "/RAM_A6") (class "Default")
      (node (ref "R343") (pin "1") (pinfunction "1_1") (pintype "passive"))
    )
    (net (code "162") (name "/RAM_A7") (class "Default")
      (node (ref "R352") (pin "1") (pinfunction "1_1") (pintype "passive"))
    )
    (net (code "163") (name "/RAM_A8") (class "Default")
      (node (ref "R347") (pin "1") (pinfunction "1_1") (pintype "passive"))
    )
    (net (code "164") (name "/RAM_A9") (class "Default")
      (node (ref "R329") (pin "1") (pinfunction "1_1") (pintype "passive"))
    )
    (net (code "165") (name "/RAM_A10") (class "Default")
      (node (ref "R345") (pin "1") (pinfunction "1_1") (pintype "passive"))
    )
    (net (code "166") (name "/RAM_A11") (class "Default")
      (node (ref "R335") (pin "1") (pinfunction "1_1") (pintype "passive"))
    )
    (net (code "168") (name "/RTCBAT") (class "Default")
      (node (ref "C70") (pin "2") (pinfunction "2_2") (pintype "passive"))
      (node (ref "C80") (pin "1") (pinfunction "1_1") (pintype "passive"))
      (node (ref "C82") (pin "1") (pinfunction "1_1") (pintype "passive"))
      (node (ref "D21") (pin "2") (pinfunction "K_2") (pintype "passive"))
      (node (ref "R116") (pin "2") (pinfunction "2_2") (pintype "passive"))
      (node (ref "R248") (pin "2") (pinfunction "2_2") (pintype "passive"))
      (node (ref "U19") (pin "8") (pinfunction "VCC_8") (pintype "power_in"))
      (node (ref "U61") (pin "T11") (pinfunction "RTCBAT_T11") (pintype "input"))
    )
    (net (code "169") (name "/SA0") (class "Default")
      (node (ref "U61") (pin "E15") (pinfunction "SA0_E15") (pintype "bidirectional"))
      (node (ref "U7") (pin "11") (pinfunction "A8_11") (pintype "bidirectional"))
    )
    (net (code "170") (name "/SA1") (class "Default")
      (node (ref "U61") (pin "E16") (pinfunction "SA1_E16") (pintype "bidirectional"))
    )
    (net (code "172") (name "/SD0") (class "Default")
      (node (ref "U61") (pin "L13") (pinfunction "SD0_L13") (pintype "bidirectional"))
    )
    (net (code "173") (name "/SD1") (class "Default")
      (node (ref "U61") (pin "L16") (pinfunction "SD1_L16") (pintype "bidirectional"))
    )
    (net (code "174") (name "/SD2") (class "Default")
      (node (ref "U61") (pin "L15") (pinfunction "SD2_L15") (pintype "bidirectional"))
    )
    (net (code "175") (name "/SD3") (class "Default")
      (node (ref "U61") (pin "L14") (pinfunction "SD3_L14") (pintype "bidirectional"))
    )
    (net (code "176") (name "/SD4") (class "Default")
      (node (ref "U61") (pin "L12") (pinfunction "SD4_L12") (pintype "bidirectional"))
    )
    (net (code "177") (name "/SD5") (class "Default")
      (node (ref "U61") (pin "M16") (pinfunction "SD5_M16") (pintype "bidirectional"))
    )
    (net (code "178") (name "/SD6") (class "Default")
      (node (ref "U61") (pin "M15") (pinfunction "SD6_M15") (pintype "bidirectional"))
    )
    (net (code "179") (name "/SD7") (class "Default")
      (node (ref "U61") (pin "M12") (pinfunction "SD7_M12") (pintype "bidirectional"))
    )
    (net (code "180") (name "/SD8") (class "Default")
      (node (ref "U61") (pin "N16") (pinfunction "SD8_N16") (pintype "bidirectional"))
    )
    (net (code "181") (name "/SD9") (class "Default")
      (node (ref "U61") (pin "N15") (pinfunction "SD9_N15") (pintype "bidirectional"))
    )
    (net (code "182") (name "/SD10") (class "Default")
      (node (ref "U61") (pin "M13") (pinfunction "SD10_M13") (pintype "bidirectional"))
    )
    (net (code "183") (name "/SD11") (class "Default")
      (node (ref "U61") (pin "N14") (pinfunction "SD11_N14") (pintype "bidirectional"))
    )
    (net (code "184") (name "/SD12") (class "Default")
      (node (ref "U61") (pin "P16") (pinfunction "SD12_P16") (pintype "bidirectional"))
    )
    (net (code "185") (name "/SD13") (class "Default")
      (node (ref "U61") (pin "P15") (pinfunction "SD13_P15") (pintype "bidirectional"))
    )
    (net (code "186") (name "/SD14") (class "Default")
      (node (ref "U61") (pin "P14") (pinfunction "SD14_P14") (pintype "bidirectional"))
    )
    (net (code "187") (name "/SD15") (class "Default")
      (node (ref "U61") (pin "R16") (pinfunction "SD15_R16") (pintype "bidirectional"))
    )
    (net (code "189") (name "/U61_RAM_LCASL#") (class "Default")
      (node (ref "U61") (pin "D8") (pinfunction "LCASL#_D8") (pintype "output"))
    )
    (net (code "190") (name "/U61_RAM_LCASU#") (class "Default")
      (node (ref "U61") (pin "A9") (pinfunction "LCASU#_A9") (pintype "output"))
    )
    (net (code "191") (name "/U61_RAM_RAMWE#") (class "Default")
      (node (ref "U61") (pin "B8") (pinfunction "RAMWE#_B8") (pintype "output"))
    )
    (net (code "192") (name "/U61_RAM_RAS0") (class "Default")
      (node (ref "U61") (pin "C13") (pinfunction "RAS0_C13") (pintype "output"))
    )
    (net (code "193") (name "/U61_RAM_RAS2") (class "Default")
      (node (ref "U61") (pin "B13") (pinfunction "RAS2_B13") (pintype "output"))
    )
    (net (code "194") (name "/U61_RAM_RAS3") (class "Default")
      (node (ref "U61") (pin "A13") (pinfunction "RAS3_A13") (pintype "output"))
    )
    (net (code "195") (name "/U61_RAM_UCASL#") (class "Default")
      (node (ref "U61") (pin "A8") (pinfunction "UCASL#_A8") (pintype "output"))
    )
    (net (code "196") (name "/U61_RAM_UCASU#") (class "Default")
      (node (ref "U61") (pin "D9") (pinfunction "UCASU#_D9") (pintype "output"))
    )
    (net (code "197") (name "/U61_RTCBAT_470K") (class "Default")
      (node (ref "R248") (pin "1") (pinfunction "1_1") (pintype "passive"))
      (node (ref "U61") (pin "P10") (pinfunction "RTCBAT_Sense_P10") (pintype "bidirectional"))
    )
    (net (code "198") (name "/U71_OR1_IN2") (class "Default")
      (node (ref "U7") (pin "19") (pinfunction "B3_19") (pintype "bidirectional"))
    )
    (net (code "199") (name "/UNKNOWN1") (class "Default")
      (node (ref "U61") (pin "R13") (pinfunction "UNKNOWN1_R13") (pintype "bidirectional"))
      (node (ref "U7") (pin "4") (pinfunction "A1_4") (pintype "bidirectional"))
    )
    (net (code "200") (name "/UNKNOWN2") (class "Default")
      (node (ref "U61") (pin "N12") (pinfunction "UNKNOWN2_N12") (pintype "bidirectional"))
      (node (ref "U7") (pin "5") (pinfunction "A2_5") (pintype "bidirectional"))
    )
    (net (code "201") (name "/YMF_SA0_A0") (class "Default")
      (node (ref "U7") (pin "14") (pinfunction "B8_14") (pintype "bidirectional"))
    )
    (net (code "202") (name "/YMF_VSS_Res") (class "Default")
      (node (ref "U61") (pin "P12") (pinfunction "PCMCIA_RELATED_P12") (pintype "bidirectional"))
    )
    (net (code "203") (name "GND") (class "Default")
      (node (ref "C250") (pin "1") (pinfunction "1_1") (pintype "passive"))
      (node (ref "C251") (pin "1") (pinfunction "1_1") (pintype "passive"))
      (node (ref "C252") (pin "2") (pinfunction "2_2") (pintype "passive"))
      (node (ref "C253") (pin "2") (pinfunction "2_2") (pintype "passive"))
      (node (ref "C35") (pin "1") (pinfunction "1_1") (pintype "passive"))
      (node (ref "C69") (pin "2") (pinfunction "2_2") (pintype "passive"))
      (node (ref "C70") (pin "1") (pinfunction "1_1") (pintype "passive"))
      (node (ref "C73") (pin "1") (pinfunction "+_1") (pintype "passive"))
      (node (ref "C75") (pin "2") (pinfunction "-_2") (pintype "passive"))
      (node (ref "C76") (pin "2") (pinfunction "2_2") (pintype "passive"))
      (node (ref "C77") (pin "1") (pinfunction "+_1") (pintype "passive"))
      (node (ref "C79") (pin "2") (pinfunction "2_2") (pintype "passive"))
      (node (ref "C8") (pin "2") (pinfunction "2_2") (pintype "passive"))
      (node (ref "C80") (pin "2") (pinfunction "2_2") (pintype "passive"))
      (node (ref "C81") (pin "2") (pinfunction "-_2") (pintype "passive"))
      (node (ref "C82") (pin "2") (pinfunction "2_2") (pintype "passive"))
      (node (ref "D23") (pin "2") (pinfunction "A_2") (pintype "passive"))
      (node (ref "J4") (pin "2") (pinfunction "Pin_2_2") (pintype "passive"))
      (node (ref "R402") (pin "2") (pinfunction "2_2") (pintype "passive"))
      (node (ref "R404") (pin "2") (pinfunction "2_2") (pintype "passive"))
      (node (ref "R405") (pin "2") (pinfunction "2_2") (pintype "passive"))
      (node (ref "R406") (pin "2") (pinfunction "2_2") (pintype "passive"))
      (node (ref "R49") (pin "2") (pinfunction "2_2") (pintype "passive"))
      (node (ref "R57") (pin "2") (pinfunction "2_2") (pintype "passive"))
      (node (ref "U19") (pin "4") (pinfunction "GND_4") (pintype "power_in"))
      (node (ref "U19") (pin "5") (pinfunction "5_5") (pintype "input"))
      (node (ref "U19") (pin "7") (pinfunction "7_7") (pintype "input"))
      (node (ref "U58") (pin "3") (pinfunction "GND_3") (pintype "power_in"))
      (node (ref "U61") (pin "A1") (pinfunction "GND_A1") (pintype "power_in"))
      (node (ref "U61") (pin "A16") (pinfunction "GND_A16") (pintype "power_in"))
      (node (ref "U61") (pin "C10") (pinfunction "GND_C10") (pintype "power_in"))
      (node (ref "U61") (pin "C8") (pinfunction "GND_C8") (pintype "power_in"))
      (node (ref "U61") (pin "F11") (pinfunction "GND_F11") (pintype "power_in"))
      (node (ref "U61") (pin "H13") (pinfunction "GND_H13") (pintype "power_in"))
      (node (ref "U61") (pin "J2") (pinfunction "GND_J2") (pintype "power_in"))
      (node (ref "U61") (pin "K14") (pinfunction "GND_K14") (pintype "power_in"))
      (node (ref "U61") (pin "P8") (pinfunction "GND_P8") (pintype "power_in"))
      (node (ref "U61") (pin "T1") (pinfunction "GND_T1") (pintype "power_in"))
      (node (ref "U61") (pin "T16") (pinfunction "GND_T16") (pintype "power_in"))
      (node (ref "U7") (pin "12") (pinfunction "GND_12") (pintype "power_in"))
      (node (ref "U7") (pin "13") (pinfunction "GND_13") (pintype "power_in"))
      (node (ref "U7") (pin "23") (pinfunction "G#_23") (pintype "input"))
    )
    (net (code "204") (name "Net-(D21-A-Pad3)") (class "Default")
      (node (ref "D21") (pin "3") (pinfunction "A_3") (pintype "passive"))
      (node (ref "R31") (pin "1") (pinfunction "1_1") (pintype "passive"))
    )
    (net (code "205") (name "Net-(D23-K)") (class "Default")
      (node (ref "D21") (pin "1") (pinfunction "A_1") (pintype "passive"))
      (node (ref "D23") (pin "1") (pinfunction "K_1") (pintype "passive"))
      (node (ref "R308") (pin "1") (pinfunction "1_1") (pintype "passive"))
    )
    (net (code "206") (name "Net-(D58-K)") (class "Default")
      (node (ref "D58") (pin "1") (pinfunction "K_1") (pintype "passive"))
      (node (ref "R308") (pin "2") (pinfunction "2_2") (pintype "passive"))
    )
    (net (code "207") (name "Net-(U61-CPUCLK33)") (class "Default")
      (node (ref "R251") (pin "2") (pinfunction "2_2") (pintype "passive"))
      (node (ref "U61") (pin "J3") (pinfunction "CPUCLK33_J3") (pintype "output"))
    )
    (net (code "208") (name "Net-(U61-IOR#)") (class "Default")
      (node (ref "R326") (pin "1") (pinfunction "1_1") (pintype "passive"))
      (node (ref "U61") (pin "J15") (pinfunction "IOR#_J15") (pintype "output"))
    )
    (net (code "209") (name "Net-(U61-IOW#)") (class "Default")
      (node (ref "R318") (pin "2") (pinfunction "2_2") (pintype "passive"))
      (node (ref "U61") (pin "J14") (pinfunction "IOW#_J14") (pintype "output"))
    )
    (net (code "210") (name "Net-(U61-MEMR#)") (class "Default")
      (node (ref "R322") (pin "2") (pinfunction "2_2") (pintype "passive"))
      (node (ref "U61") (pin "F13") (pinfunction "MEMR#_F13") (pintype "bidirectional"))
    )
    (net (code "211") (name "Net-(U61-MEMW#)") (class "Default")
      (node (ref "R324") (pin "2") (pinfunction "2_2") (pintype "passive"))
      (node (ref "U61") (pin "G14") (pinfunction "MEMW#_G14") (pintype "bidirectional"))
    )
    (net (code "212") (name "Net-(U61-PS{slash}RCLR#)") (class "Default")
      (node (ref "C79") (pin "1") (pinfunction "1_1") (pintype "passive"))
      (node (ref "R116") (pin "1") (pinfunction "1_1") (pintype "passive"))
      (node (ref "U61") (pin "M11") (pinfunction "PS/RCLR#_M11") (pintype "bidirectional"))
    )
    (net (code "213") (name "Net-(U61-PWRGD)") (class "Default")
      (node (ref "R96") (pin "2") (pinfunction "2_2") (pintype "passive"))
      (node (ref "U19") (pin "2") (pinfunction "2_2") (pintype "input"))
      (node (ref "U61") (pin "R10") (pinfunction "PWRGD_R10") (pintype "output"))
    )
    (net (code "214") (name "Net-(U61-PWRGD_P13)") (class "Default")
      (node (ref "R49") (pin "1") (pinfunction "1_1") (pintype "passive"))
      (node (ref "U61") (pin "P13") (pinfunction "PWRGD_P13_P13") (pintype "output"))
      (node (ref "U7") (pin "6") (pinfunction "A3_6") (pintype "bidirectional"))
    )
    (net (code "215") (name "Net-(U61-RAMA0)") (class "Default")
      (node (ref "R346") (pin "2") (pinfunction "2_2") (pintype "passive"))
      (node (ref "U61") (pin "C12") (pinfunction "RAMA0_C12") (pintype "bidirectional"))
    )
    (net (code "216") (name "Net-(U61-RAMA1)") (class "Default")
      (node (ref "R338") (pin "2") (pinfunction "2_2") (pintype "passive"))
      (node (ref "U61") (pin "E12") (pinfunction "RAMA1_E12") (pintype "bidirectional"))
    )
    (net (code "217") (name "Net-(U61-RAMA2)") (class "Default")
      (node (ref "R342") (pin "2") (pinfunction "2_2") (pintype "passive"))
      (node (ref "U61") (pin "B12") (pinfunction "RAMA2_B12") (pintype "bidirectional"))
    )
    (net (code "218") (name "Net-(U61-RAMA3)") (class "Default")
      (node (ref "R337") (pin "2") (pinfunction "2_2") (pintype "passive"))
      (node (ref "U61") (pin "E11") (pinfunction "RAMA3_E11") (pintype "bidirectional"))
    )
    (net (code "219") (name "Net-(U61-RAMA4)") (class "Default")
      (node (ref "R334") (pin "2") (pinfunction "2_2") (pintype "passive"))
      (node (ref "U61") (pin "C11") (pinfunction "RAMA4_C11") (pintype "bidirectional"))
    )
    (net (code "220") (name "Net-(U61-RAMA5)") (class "Default")
      (node (ref "R333") (pin "2") (pinfunction "2_2") (pintype "passive"))
      (node (ref "U61") (pin "B11") (pinfunction "RAMA5_B11") (pintype "bidirectional"))
    )
    (net (code "221") (name "Net-(U61-RAMA6)") (class "Default")
      (node (ref "R343") (pin "2") (pinfunction "2_2") (pintype "passive"))
      (node (ref "U61") (pin "A11") (pinfunction "RAMA6_A11") (pintype "bidirectional"))
    )
    (net (code "222") (name "Net-(U61-RAMA7)") (class "Default")
      (node (ref "R352") (pin "2") (pinfunction "2_2") (pintype "passive"))
      (node (ref "U61") (pin "D11") (pinfunction "RAMA7_D11") (pintype "bidirectional"))
    )
    (net (code "223") (name "Net-(U61-RAMA8)") (class "Default")
      (node (ref "R347") (pin "2") (pinfunction "2_2") (pintype "passive"))
      (node (ref "U61") (pin "B10") (pinfunction "RAMA8_B10") (pintype "bidirectional"))
    )
    (net (code "224") (name "Net-(U61-RAMA9)") (class "Default")
      (node (ref "R329") (pin "2") (pinfunction "2_2") (pintype "passive"))
      (node (ref "U61") (pin "A10") (pinfunction "RAMA9_A10") (pintype "bidirectional"))
    )
    (net (code "225") (name "Net-(U61-RAMA10)") (class "Default")
      (node (ref "R345") (pin "2") (pinfunction "2_2") (pintype "passive"))
      (node (ref "U61") (pin "D10") (pinfunction "RAMA10_D10") (pintype "bidirectional"))
    )
    (net (code "226") (name "Net-(U61-RAMA11)") (class "Default")
      (node (ref "R335") (pin "2") (pinfunction "2_2") (pintype "passive"))
      (node (ref "U61") (pin "C9") (pinfunction "RAMA11_C9") (pintype "bidirectional"))
    )
    (net (code "227") (name "Net-(U61-RESET)") (class "Default")
      (node (ref "U58") (pin "2") (pinfunction "2_2") (pintype "input"))
      (node (ref "U61") (pin "N13") (pinfunction "RESET_N13") (pintype "bidirectional"))
    )
    (net (code "228") (name "Net-(U61-RTCOSCI)") (class "Default")
      (node (ref "C251") (pin "2") (pinfunction "2_2") (pintype "passive"))
      (node (ref "U61") (pin "R11") (pinfunction "RTCOSCI_R11") (pintype "bidirectional"))
      (node (ref "X3") (pin "1") (pinfunction "1_1") (pintype "passive"))
    )
    (net (code "229") (name "Net-(U61-RTCOSCO)") (class "Default")
      (node (ref "C250") (pin "2") (pinfunction "2_2") (pintype "passive"))
      (node (ref "U61") (pin "P11") (pinfunction "RTCOSCO_P11") (pintype "bidirectional"))
      (node (ref "X3") (pin "4") (pinfunction "4_4") (pintype "passive"))
    )
    (net (code "230") (name "Net-(U61-TP1)") (class "Default")
      (node (ref "J14") (pin "1") (pinfunction "1_1") (pintype "passive"))
      (node (ref "U61") (pin "T14") (pinfunction "TP1_T14") (pintype "bidirectional"))
    )
    (net (code "231") (name "Net-(U61-UNKNOWN3)") (class "Default")
      (node (ref "R246") (pin "2") (pinfunction "2_2") (pintype "passive"))
      (node (ref "U61") (pin "R8") (pinfunction "UNKNOWN3_R8") (pintype "bidirectional"))
    )
    (net (code "232") (name "Net-(U61-UNKNOWN4)") (class "Default")
      (node (ref "R249") (pin "2") (pinfunction "2_2") (pintype "passive"))
      (node (ref "U61") (pin "N8") (pinfunction "UNKNOWN4_N8") (pintype "bidirectional"))
    )
    (net (code "233") (name "PNET1") (class "Default")
      (node (ref "C252") (pin "1") (pinfunction "1_1") (pintype "passive"))
      (node (ref "C253") (pin "1") (pinfunction "1_1") (pintype "passive"))
      (node (ref "C69") (pin "1") (pinfunction "1_1") (pintype "passive"))
      (node (ref "C73") (pin "2") (pinfunction "-_2") (pintype "passive"))
      (node (ref "C75") (pin "1") (pinfunction "+_1") (pintype "passive"))
      (node (ref "C77") (pin "2") (pinfunction "-_2") (pintype "passive"))
      (node (ref "R246") (pin "1") (pinfunction "1_1") (pintype "passive"))
      (node (ref "R249") (pin "1") (pinfunction "1_1") (pintype "passive"))
      (node (ref "R400") (pin "2") (pinfunction "2_2") (pintype "passive"))
      (node (ref "R401") (pin "2") (pinfunction "2_2") (pintype "passive"))
      (node (ref "R403") (pin "2") (pinfunction "2_2") (pintype "passive"))
      (node (ref "R96") (pin "1") (pinfunction "1_1") (pintype "passive"))
      (node (ref "U19") (pin "1") (pinfunction "1_1") (pintype "input"))
      (node (ref "U61") (pin "A12") (pinfunction "VCC_A12") (pintype "power_in"))
      (node (ref "U61") (pin "B15") (pinfunction "VCC_B15") (pintype "power_in"))
      (node (ref "U61") (pin "B2") (pinfunction "VCC_B2") (pintype "power_in"))
      (node (ref "U61") (pin "B9") (pinfunction "VCC_B9") (pintype "power_in"))
      (node (ref "U61") (pin "J4") (pinfunction "VCC_J4") (pintype "power_in"))
      (node (ref "U61") (pin "K4") (pinfunction "VCC_K4") (pintype "power_in"))
      (node (ref "U61") (pin "M5") (pinfunction "VCC_M5") (pintype "power_in"))
      (node (ref "U7") (pin "1") (pinfunction "VCCA_1") (pintype "power_in"))
      (node (ref "U7") (pin "2") (pinfunction "DIR_2") (pintype "input"))
    )
    (net (code "234") (name "PNET5") (class "Default")
      (node (ref "C35") (pin "2") (pinfunction "2_2") (pintype "passive"))
      (node (ref "U7") (pin "24") (pinfunction "VCCB_24") (pintype "power_in"))
    )
    (net (code "235") (name "PNET7") (class "Default")
      (node (ref "C76") (pin "1") (pinfunction "1_1") (pintype "passive"))
      (node (ref "C81") (pin "1") (pinfunction "+_1") (pintype "passive"))
      (node (ref "R323") (pin "1") (pinfunction "1_1") (pintype "passive"))
      (node (ref "U58") (pin "5") (pinfunction "VCC_5") (pintype "power_in"))
      (node (ref "U61") (pin "F14") (pinfunction "VCCIO_F14") (pintype "power_in"))
      (node (ref "U61") (pin "M14") (pinfunction "VCCIO_M14") (pintype "power_in"))
    )
    (net (code "236") (name "VCC") (class "Default")
      (node (ref "D58") (pin "2") (pinfunction "A_2") (pintype "passive"))
    )
    (net (code "237") (name "unconnected-(D58-common-Pad3)") (class "Default")
      (node (ref "D58") (pin "3") (pinfunction "common_3") (pintype "passive+no_connect"))
    )
    (net (code "238") (name "unconnected-(U7-B1-Pad21)") (class "Default")
      (node (ref "U7") (pin "21") (pinfunction "B1_21") (pintype "bidirectional+no_connect"))
    )
    (net (code "239") (name "unconnected-(U7-B2-Pad20)") (class "Default")
      (node (ref "U7") (pin "20") (pinfunction "B2_20") (pintype "bidirectional+no_connect"))
    )
    (net (code "240") (name "unconnected-(U19-Pad3)") (class "Default")
      (node (ref "U19") (pin "3") (pinfunction "3_3") (pintype "tri_state+no_connect"))
    )
    (net (code "241") (name "unconnected-(U58-NC-Pad1)") (class "Default")
      (node (ref "U58") (pin "1") (pinfunction "NC_1") (pintype "input"))
    )
    (net (code "242") (name "unconnected-(U61-PadA14)") (class "Default")
      (node (ref "U61") (pin "A14") (pinfunction "A14_A14") (pintype "input"))
    )
    (net (code "243") (name "unconnected-(U61-PadA15)") (class "Default")
      (node (ref "U61") (pin "A15") (pinfunction "A15_A15") (pintype "input"))
    )
    (net (code "244") (name "unconnected-(U61-PadB14)") (class "Default")
      (node (ref "U61") (pin "B14") (pinfunction "B14_B14") (pintype "input"))
    )
    (net (code "245") (name "unconnected-(U61-PadC14)") (class "Default")
      (node (ref "U61") (pin "C14") (pinfunction "C14_C14") (pintype "input"))
    )
    (net (code "246") (name "unconnected-(U61-PadE7)") (class "Default")
      (node (ref "U61") (pin "E7") (pinfunction "E7_E7") (pintype "input"))
    )
    (net (code "247") (name "unconnected-(U61-PadE8)") (class "Default")
      (node (ref "U61") (pin "E8") (pinfunction "E8_E8") (pintype "input"))
    )
    (net (code "248") (name "unconnected-(U61-PadE9)") (class "Default")
      (node (ref "U61") (pin "E9") (pinfunction "E9_E9") (pintype "input"))
    )
    (net (code "249") (name "unconnected-(U61-PadE10)") (class "Default")
      (node (ref "U61") (pin "E10") (pinfunction "E10_E10") (pintype "input"))
    )
    (net (code "250") (name "unconnected-(U61-PadF3)") (class "Default")
      (node (ref "U61") (pin "F3") (pinfunction "F3_F3") (pintype "input"))
    )
    (net (code "251") (name "unconnected-(U61-PadF5)") (class "Default")
      (node (ref "U61") (pin "F5") (pinfunction "F5_F5") (pintype "input"))
    )
    (net (code "252") (name "unconnected-(U61-PadF7)") (class "Default")
      (node (ref "U61") (pin "F7") (pinfunction "F7_F7") (pintype "input"))
    )
    (net (code "253") (name "unconnected-(U61-PadF8)") (class "Default")
      (node (ref "U61") (pin "F8") (pinfunction "F8_F8") (pintype "input"))
    )
    (net (code "254") (name "unconnected-(U61-PadF9)") (class "Default")
      (node (ref "U61") (pin "F9") (pinfunction "F9_F9") (pintype "input"))
    )
    (net (code "255") (name "unconnected-(U61-PadF10)") (class "Default")
      (node (ref "U61") (pin "F10") (pinfunction "F10_F10") (pintype "input"))
    )
    (net (code "256") (name "unconnected-(U61-PadF15)") (class "Default")
      (node (ref "U61") (pin "F15") (pinfunction "F15_F15") (pintype "input"))
    )
    (net (code "257") (name "unconnected-(U61-PadF16)") (class "Default")
      (node (ref "U61") (pin "F16") (pinfunction "F16_F16") (pintype "input"))
    )
    (net (code "258") (name "unconnected-(U61-PadG5)") (class "Default")
      (node (ref "U61") (pin "G5") (pinfunction "G5_G5") (pintype "input"))
    )
    (net (code "259") (name "unconnected-(U61-PadG6)") (class "Default")
      (node (ref "U61") (pin "G6") (pinfunction "G6_G6") (pintype "input"))
    )
    (net (code "260") (name "unconnected-(U61-PadG7)") (class "Default")
      (node (ref "U61") (pin "G7") (pinfunction "G7_G7") (pintype "input"))
    )
    (net (code "261") (name "unconnected-(U61-PadG8)") (class "Default")
      (node (ref "U61") (pin "G8") (pinfunction "G8_G8") (pintype "input"))
    )
    (net (code "262") (name "unconnected-(U61-PadG9)") (class "Default")
      (node (ref "U61") (pin "G9") (pinfunction "G9_G9") (pintype "input"))
    )
    (net (code "263") (name "unconnected-(U61-PadG10)") (class "Default")
      (node (ref "U61") (pin "G10") (pinfunction "G10_G10") (pintype "input"))
    )
    (net (code "264") (name "unconnected-(U61-PadG11)") (class "Default")
      (node (ref "U61") (pin "G11") (pinfunction "G11_G11") (pintype "input"))
    )
    (net (code "265") (name "unconnected-(U61-PadG12)") (class "Default")
      (node (ref "U61") (pin "G12") (pinfunction "G12_G12") (pintype "input"))
    )
    (net (code "266") (name "unconnected-(U61-PadH5)") (class "Default")
      (node (ref "U61") (pin "H5") (pinfunction "H5_H5") (pintype "input"))
    )
    (net (code "267") (name "unconnected-(U61-PadH6)") (class "Default")
      (node (ref "U61") (pin "H6") (pinfunction "H6_H6") (pintype "input"))
    )
    (net (code "268") (name "unconnected-(U61-PadH7)") (class "Default")
      (node (ref "U61") (pin "H7") (pinfunction "H7_H7") (pintype "input"))
    )
    (net (code "269") (name "unconnected-(U61-PadH8)") (class "Default")
      (node (ref "U61") (pin "H8") (pinfunction "H8_H8") (pintype "input"))
    )
    (net (code "270") (name "unconnected-(U61-PadH9)") (class "Default")
      (node (ref "U61") (pin "H9") (pinfunction "H9_H9") (pintype "input"))
    )
    (net (code "271") (name "unconnected-(U61-PadH10)") (class "Default")
      (node (ref "U61") (pin "H10") (pinfunction "H10_H10") (pintype "input"))
    )
    (net (code "272") (name "unconnected-(U61-PadH11)") (class "Default")
      (node (ref "U61") (pin "H11") (pinfunction "H11_H11") (pintype "input"))
    )
    (net (code "273") (name "unconnected-(U61-PadH12)") (class "Default")
      (node (ref "U61") (pin "H12") (pinfunction "H12_H12") (pintype "input"))
    )
    (net (code "274") (name "unconnected-(U61-PadJ5)") (class "Default")
      (node (ref "U61") (pin "J5") (pinfunction "J5_J5") (pintype "input"))
    )
    (net (code "275") (name "unconnected-(U61-PadJ6)") (class "Default")
      (node (ref "U61") (pin "J6") (pinfunction "J6_J6") (pintype "input"))
    )
    (net (code "276") (name "unconnected-(U61-PadJ7)") (class "Default")
      (node (ref "U61") (pin "J7") (pinfunction "J7_J7") (pintype "input"))
    )
    (net (code "277") (name "unconnected-(U61-PadJ8)") (class "Default")
      (node (ref "U61") (pin "J8") (pinfunction "J8_J8") (pintype "input"))
    )
    (net (code "278") (name "unconnected-(U61-PadJ9)") (class "Default")
      (node (ref "U61") (pin "J9") (pinfunction "J9_J9") (pintype "input"))
    )
    (net (code "279") (name "unconnected-(U61-PadJ10)") (class "Default")
      (node (ref "U61") (pin "J10") (pinfunction "J10_J10") (pintype "input"))
    )
    (net (code "280") (name "unconnected-(U61-PadJ11)") (class "Default")
      (node (ref "U61") (pin "J11") (pinfunction "J11_J11") (pintype "input"))
    )
    (net (code "281") (name "unconnected-(U61-PadJ12)") (class "Default")
      (node (ref "U61") (pin "J12") (pinfunction "J12_J12") (pintype "input"))
    )
    (net (code "282") (name "unconnected-(U61-PadK5)") (class "Default")
      (node (ref "U61") (pin "K5") (pinfunction "K5_K5") (pintype "input"))
    )
    (net (code "283") (name "unconnected-(U61-PadK6)") (class "Default")
      (node (ref "U61") (pin "K6") (pinfunction "K6_K6") (pintype "input"))
    )
    (net (code "284") (name "unconnected-(U61-PadK7)") (class "Default")
      (node (ref "U61") (pin "K7") (pinfunction "K7_K7") (pintype "input"))
    )
    (net (code "285") (name "unconnected-(U61-PadK8)") (class "Default")
      (node (ref "U61") (pin "K8") (pinfunction "K8_K8") (pintype "input"))
    )
    (net (code "286") (name "unconnected-(U61-PadK9)") (class "Default")
      (node (ref "U61") (pin "K9") (pinfunction "K9_K9") (pintype "input"))
    )
    (net (code "287") (name "unconnected-(U61-PadK10)") (class "Default")
      (node (ref "U61") (pin "K10") (pinfunction "K10_K10") (pintype "input"))
    )
    (net (code "288") (name "unconnected-(U61-PadK11)") (class "Default")
      (node (ref "U61") (pin "K11") (pinfunction "K11_K11") (pintype "input"))
    )
    (net (code "289") (name "unconnected-(U61-PadK12)") (class "Default")
      (node (ref "U61") (pin "K12") (pinfunction "K12_K12") (pintype "input"))
    )
    (net (code "290") (name "unconnected-(U61-PadK13)") (class "Default")
      (node (ref "U61") (pin "K13") (pinfunction "K13_K13") (pintype "input"))
    )
    (net (code "291") (name "unconnected-(U61-PadK16)") (class "Default")
      (node (ref "U61") (pin "K16") (pinfunction "K16_K16") (pintype "input"))
    )
    (net (code "292") (name "unconnected-(U61-PadL7)") (class "Default")
      (node (ref "U61") (pin "L7") (pinfunction "L7_L7") (pintype "input"))
    )
    (net (code "293") (name "unconnected-(U61-PadL8)") (class "Default")
      (node (ref "U61") (pin "L8") (pinfunction "L8_L8") (pintype "input"))
    )
    (net (code "294") (name "unconnected-(U61-PadL9)") (class "Default")
      (node (ref "U61") (pin "L9") (pinfunction "L9_L9") (pintype "input"))
    )
    (net (code "295") (name "unconnected-(U61-PadL10)") (class "Default")
      (node (ref "U61") (pin "L10") (pinfunction "L10_L10") (pintype "input"))
    )
    (net (code "296") (name "unconnected-(U61-PadL11)") (class "Default")
      (node (ref "U61") (pin "L11") (pinfunction "L11_L11") (pintype "input"))
    )
    (net (code "297") (name "unconnected-(U61-PadM7)") (class "Default")
      (node (ref "U61") (pin "M7") (pinfunction "M7_M7") (pintype "input"))
    )
    (net (code "298") (name "unconnected-(U61-PadM8)") (class "Default")
      (node (ref "U61") (pin "M8") (pinfunction "M8_M8") (pintype "input"))
    )
    (net (code "299") (name "unconnected-(U61-PadM9)") (class "Default")
      (node (ref "U61") (pin "M9") (pinfunction "M9_M9") (pintype "input"))
    )
    (net (code "300") (name "unconnected-(U61-PadM10)") (class "Default")
      (node (ref "U61") (pin "M10") (pinfunction "M10_M10") (pintype "input"))
    )
    (net (code "301") (name "unconnected-(U61-PadN10)") (class "Default")
      (node (ref "U61") (pin "N10") (pinfunction "N10_N10") (pintype "input"))
    )
    (net (code "302") (name "unconnected-(U61-PadR12)") (class "Default")
      (node (ref "U61") (pin "R12") (pinfunction "R12_R12") (pintype "input"))
    )
    (net (code "303") (name "unconnected-(U61-PadT8)") (class "Default")
      (node (ref "U61") (pin "T8") (pinfunction "T8_T8") (pintype "input"))
    )
    (net (code "304") (name "unconnected-(U61-RAS1-PadD12)") (class "Default")
      (node (ref "U61") (pin "D12") (pinfunction "RAS1_D12") (pintype "output+no_connect"))
    )
    (net (code "305") (name "unconnected-(X3-Pad2)") (class "Default")
      (node (ref "X3") (pin "2") (pinfunction "2_2") (pintype "passive+no_connect"))
    )
    (net (code "306") (name "unconnected-(X3-Pad3)") (class "Default")
      (node (ref "X3") (pin "3") (pinfunction "3_3") (pintype "passive+no_connect"))
    )
  )
)
